# Electronic_Load.net
KiCad netlist of a schematic drawn in Altium Designer
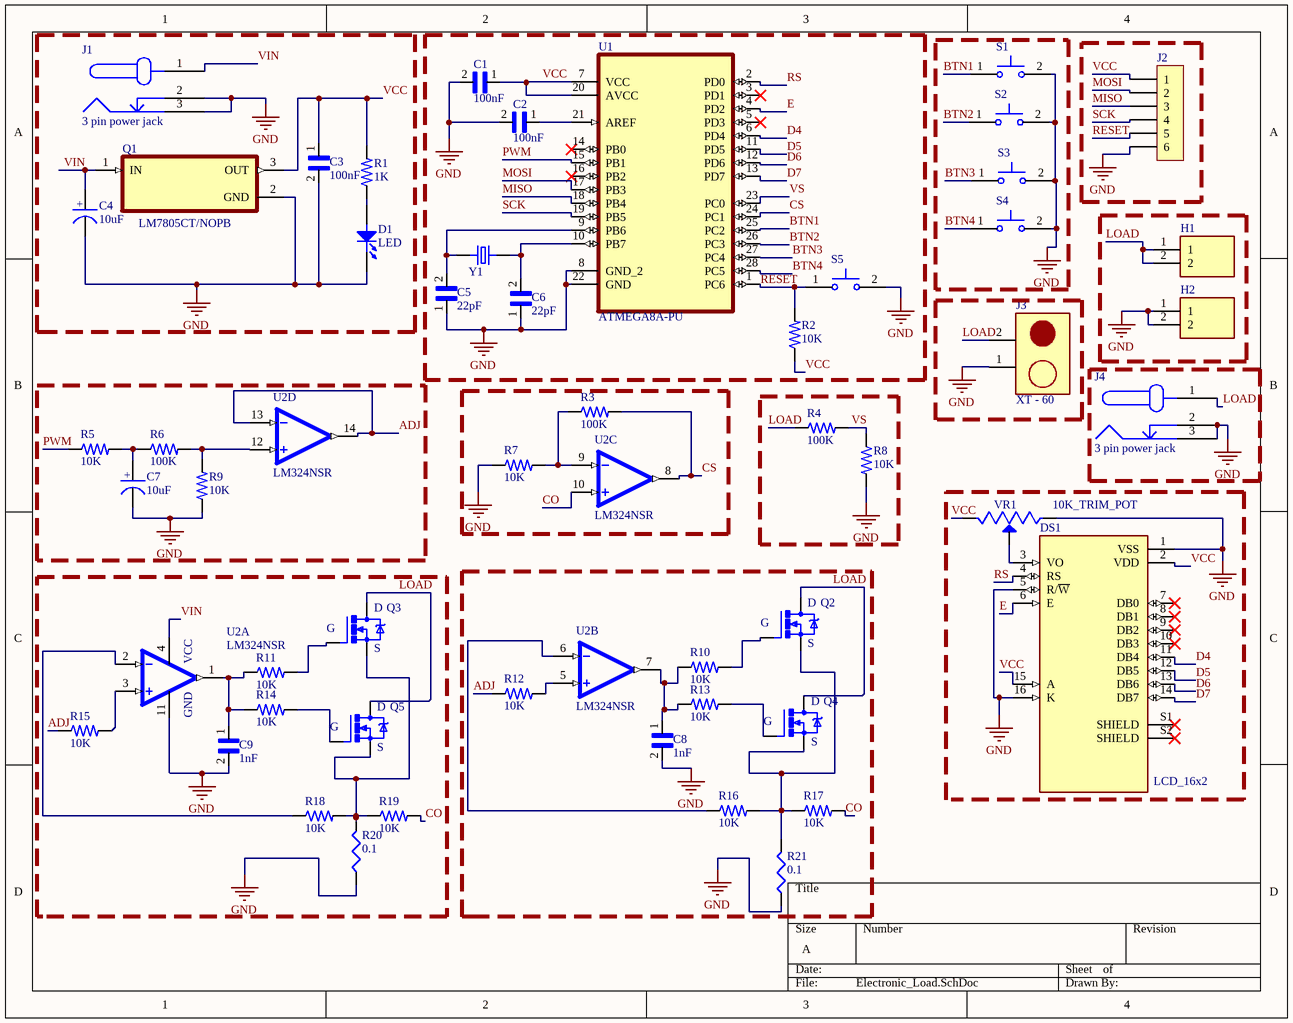
[diagram p0: Electronic_Load.SchDoc]

(export (version "E")
  (design (tool "Eeschema 10.0.6"))
  (components
    (comp (ref "C1")
      (value "100nF")
      (footprint "Cap_nonpolarized_2.5mm")
      (description "ceramic cap")
      (fields (field (name "MP") "GRM31CC80E157ME11K") (field (name "MF") "Murata"))
      (libsource (lib "Electronic_Load") (part "CAP1206"))
    )
    (comp (ref "C2")
      (value "100nF")
      (footprint "Cap_nonpolarized_2.5mm")
      (description "ceramic cap")
      (fields (field (name "MP") "GRM31CC80E157ME11K") (field (name "MF") "Murata"))
      (libsource (lib "Electronic_Load") (part "CAP1206"))
    )
    (comp (ref "C3")
      (value "100nF")
      (footprint "Cap_nonpolarized_2.5mm")
      (description "ceramic cap")
      (fields (field (name "MP") "GRM31CC80E157ME11K") (field (name "MF") "Murata"))
      (libsource (lib "") (part "CAP1206_1"))
    )
    (comp (ref "C4")
      (value "10uF")
      (footprint "CP_Radial_D4.0mm_P1.50mm")
      (description "Generial polarized capacitor for through hole or SMD capacitors")
      (libsource (lib "Electronic_Load") (part "Polarized capacitors"))
    )
    (comp (ref "C5")
      (value "22pF")
      (footprint "Cap_nonpolarized_2.5mm")
      (description "ceramic cap")
      (fields (field (name "MP") "GRM31CC80E157ME11K") (field (name "MF") "Murata"))
      (libsource (lib "") (part "CAP1206_2"))
    )
    (comp (ref "C6")
      (value "22pF")
      (footprint "Cap_nonpolarized_2.5mm")
      (description "ceramic cap")
      (fields (field (name "MP") "GRM31CC80E157ME11K") (field (name "MF") "Murata"))
      (libsource (lib "") (part "CAP1206_2"))
    )
    (comp (ref "C7")
      (value "10uF")
      (footprint "CP_Radial_D4.0mm_P1.50mm")
      (description "Generial polarized capacitor for through hole or SMD capacitors")
      (libsource (lib "Electronic_Load") (part "Polarized capacitors"))
    )
    (comp (ref "C8")
      (value "1nF")
      (footprint "Cap_nonpolarized_2.5mm")
      (description "ceramic cap")
      (fields (field (name "MP") "GRM31CC80E157ME11K") (field (name "MF") "Murata"))
      (libsource (lib "") (part "CAP1206_1"))
    )
    (comp (ref "C9")
      (value "1nF")
      (footprint "Cap_nonpolarized_2.5mm")
      (description "ceramic cap")
      (fields (field (name "MP") "GRM31CC80E157ME11K") (field (name "MF") "Murata"))
      (libsource (lib "") (part "CAP1206_1"))
    )
    (comp (ref "D1")
      (value "LED")
      (footprint "LED_TH_2.54mm")
      (libsource (lib "Electronic_Load") (part "LED"))
    )
    (comp (ref "DS1")
      (value "LCD_16x2")
      (footprint "LCD_16x2")
      (description "Display: LCD; alphanumeric; STN Negative; 16x2; blue; LED; PIN: 16")
      (fields (field (name "MF") "Raystar") (field (name "MP") "RC1602B-BIW-CSV"))
      (libsource (lib "Electronic_Load") (part "LCD_16x2"))
    )
    (comp (ref "H1")
      (value "Terminal PCB Male Flat 6.3mm")
      (footprint "Terminal PCB Male Flat 6.3mm")
      (description "PCR250 - Valcon PCB Mount Spade Terminal, 12.1mm PCB Profile")
      (fields (field (name "MP") "PCR250"))
      (libsource (lib "Electronic_Load") (part "Terminal PCB Male Flat 6.3mm"))
    )
    (comp (ref "H2")
      (value "Terminal PCB Male Flat 6.3mm")
      (footprint "Terminal PCB Male Flat 6.3mm")
      (description "PCR250 - Valcon PCB Mount Spade Terminal, 12.1mm PCB Profile")
      (fields (field (name "MP") "PCR250"))
      (libsource (lib "Electronic_Load") (part "Terminal PCB Male Flat 6.3mm"))
    )
    (comp (ref "J1")
      (value "3 pin power jack")
      (footprint "DC_POWER_JACK_2.7MM")
      (description "DC Power Jack / generic 3 pins connector")
      (libsource (lib "Electronic_Load") (part "DC Power Jack"))
    )
    (comp (ref "J2")
      (value "6 pin socket")
      (footprint "Jst - XH - 6pins")
      (libsource (lib "Electronic_Load") (part "Jst - XH -6pins"))
    )
    (comp (ref "J3")
      (value "XT - 60")
      (footprint "XT-60")
      (libsource (lib "Electronic_Load") (part "XT - 60"))
    )
    (comp (ref "J4")
      (value "3 pin power jack")
      (footprint "DC_POWER_JACK_2.7MM")
      (description "DC Power Jack / generic 3 pins connector")
      (libsource (lib "Electronic_Load") (part "DC Power Jack"))
    )
    (comp (ref "Q1")
      (value "LM7805CT/NOPB")
      (footprint "TO254P1054X470X1955-3")
      (libsource (lib "Electronic_Load") (part "LM7805CT/NOPB"))
    )
    (comp (ref "Q2")
      (value "NTP30N06L")
      (footprint "NTP30N06L")
      (description "N-Channel 100 V 9.2A (Tc) 3.7W (Ta), 60W (Tc) Surface Mount D2PAK")
      (fields (field (name "MP") "IRF520") (field (name "MF") "Vishay Siliconix"))
      (libsource (lib "Electronic_Load") (part "NTP30N06L"))
    )
    (comp (ref "Q3")
      (value "NTP30N06L")
      (footprint "NTP30N06L")
      (description "N-Channel 100 V 9.2A (Tc) 3.7W (Ta), 60W (Tc) Surface Mount D2PAK")
      (fields (field (name "MP") "IRF520") (field (name "MF") "Vishay Siliconix"))
      (libsource (lib "Electronic_Load") (part "NTP30N06L"))
    )
    (comp (ref "Q4")
      (value "NTP30N06L")
      (footprint "NTP30N06L")
      (description "N-Channel 100 V 9.2A (Tc) 3.7W (Ta), 60W (Tc) Surface Mount D2PAK")
      (fields (field (name "MP") "IRF520") (field (name "MF") "Vishay Siliconix"))
      (libsource (lib "Electronic_Load") (part "NTP30N06L"))
    )
    (comp (ref "Q5")
      (value "NTP30N06L")
      (footprint "NTP30N06L")
      (description "N-Channel 100 V 9.2A (Tc) 3.7W (Ta), 60W (Tc) Surface Mount D2PAK")
      (fields (field (name "MP") "IRF520") (field (name "MF") "Vishay Siliconix"))
      (libsource (lib "Electronic_Load") (part "NTP30N06L"))
    )
    (comp (ref "R1")
      (value "1K")
      (footprint "resistor_through hole")
      (description "RES 0.24 OHM 1% 1/4W 1206")
      (fields (field (name "MF") "TE Connectivity") (field (name "MP") "2-1879462-9"))
      (libsource (lib "Electronic_Load") (part "1206_RESISTOR"))
    )
    (comp (ref "R2")
      (value "10K")
      (footprint "resistor_through hole")
      (description "RES 0.24 OHM 1% 1/4W 1206")
      (fields (field (name "MF") "TE Connectivity") (field (name "MP") "2-1879462-9"))
      (libsource (lib "Electronic_Load") (part "1206_RESISTOR"))
    )
    (comp (ref "R3")
      (value "100K")
      (footprint "resistor_through hole")
      (description "RES 0.24 OHM 1% 1/4W 1206")
      (fields (field (name "MF") "TE Connectivity") (field (name "MP") "2-1879462-9"))
      (libsource (lib "Electronic_Load") (part "1206_RESISTOR"))
    )
    (comp (ref "R4")
      (value "100K")
      (footprint "resistor_through hole")
      (description "RES 0.24 OHM 1% 1/4W 1206")
      (fields (field (name "MF") "TE Connectivity") (field (name "MP") "2-1879462-9"))
      (libsource (lib "Electronic_Load") (part "1206_RESISTOR"))
    )
    (comp (ref "R5")
      (value "10K")
      (footprint "resistor_through hole")
      (description "RES 0.24 OHM 1% 1/4W 1206")
      (fields (field (name "MF") "TE Connectivity") (field (name "MP") "2-1879462-9"))
      (libsource (lib "Electronic_Load") (part "1206_RESISTOR"))
    )
    (comp (ref "R6")
      (value "100K")
      (footprint "resistor_through hole")
      (description "RES 0.24 OHM 1% 1/4W 1206")
      (fields (field (name "MF") "TE Connectivity") (field (name "MP") "2-1879462-9"))
      (libsource (lib "Electronic_Load") (part "1206_RESISTOR"))
    )
    (comp (ref "R7")
      (value "10K")
      (footprint "resistor_through hole")
      (description "RES 0.24 OHM 1% 1/4W 1206")
      (fields (field (name "MF") "TE Connectivity") (field (name "MP") "2-1879462-9"))
      (libsource (lib "Electronic_Load") (part "1206_RESISTOR"))
    )
    (comp (ref "R8")
      (value "10K")
      (footprint "resistor_through hole")
      (description "RES 0.24 OHM 1% 1/4W 1206")
      (fields (field (name "MF") "TE Connectivity") (field (name "MP") "2-1879462-9"))
      (libsource (lib "Electronic_Load") (part "1206_RESISTOR"))
    )
    (comp (ref "R9")
      (value "10K")
      (footprint "resistor_through hole")
      (description "RES 0.24 OHM 1% 1/4W 1206")
      (fields (field (name "MF") "TE Connectivity") (field (name "MP") "2-1879462-9"))
      (libsource (lib "Electronic_Load") (part "1206_RESISTOR"))
    )
    (comp (ref "R10")
      (value "10K")
      (footprint "resistor_through hole")
      (description "RES 0.24 OHM 1% 1/4W 1206")
      (fields (field (name "MF") "TE Connectivity") (field (name "MP") "2-1879462-9"))
      (libsource (lib "Electronic_Load") (part "1206_RESISTOR"))
    )
    (comp (ref "R11")
      (value "10K")
      (footprint "resistor_through hole")
      (description "RES 0.24 OHM 1% 1/4W 1206")
      (fields (field (name "MF") "TE Connectivity") (field (name "MP") "2-1879462-9"))
      (libsource (lib "Electronic_Load") (part "1206_RESISTOR"))
    )
    (comp (ref "R12")
      (value "10K")
      (footprint "resistor_through hole")
      (description "RES 0.24 OHM 1% 1/4W 1206")
      (fields (field (name "MF") "TE Connectivity") (field (name "MP") "2-1879462-9"))
      (libsource (lib "Electronic_Load") (part "1206_RESISTOR"))
    )
    (comp (ref "R13")
      (value "10K")
      (footprint "resistor_through hole")
      (description "RES 0.24 OHM 1% 1/4W 1206")
      (fields (field (name "MF") "TE Connectivity") (field (name "MP") "2-1879462-9"))
      (libsource (lib "Electronic_Load") (part "1206_RESISTOR"))
    )
    (comp (ref "R14")
      (value "10K")
      (footprint "resistor_through hole")
      (description "RES 0.24 OHM 1% 1/4W 1206")
      (fields (field (name "MF") "TE Connectivity") (field (name "MP") "2-1879462-9"))
      (libsource (lib "Electronic_Load") (part "1206_RESISTOR"))
    )
    (comp (ref "R15")
      (value "10K")
      (footprint "resistor_through hole")
      (description "RES 0.24 OHM 1% 1/4W 1206")
      (fields (field (name "MF") "TE Connectivity") (field (name "MP") "2-1879462-9"))
      (libsource (lib "Electronic_Load") (part "1206_RESISTOR"))
    )
    (comp (ref "R16")
      (value "10K")
      (footprint "resistor_through hole")
      (description "RES 0.24 OHM 1% 1/4W 1206")
      (fields (field (name "MF") "TE Connectivity") (field (name "MP") "2-1879462-9"))
      (libsource (lib "Electronic_Load") (part "1206_RESISTOR"))
    )
    (comp (ref "R17")
      (value "10K")
      (footprint "resistor_through hole")
      (description "RES 0.24 OHM 1% 1/4W 1206")
      (fields (field (name "MF") "TE Connectivity") (field (name "MP") "2-1879462-9"))
      (libsource (lib "Electronic_Load") (part "1206_RESISTOR"))
    )
    (comp (ref "R18")
      (value "10K")
      (footprint "resistor_through hole")
      (description "RES 0.24 OHM 1% 1/4W 1206")
      (fields (field (name "MF") "TE Connectivity") (field (name "MP") "2-1879462-9"))
      (libsource (lib "Electronic_Load") (part "1206_RESISTOR"))
    )
    (comp (ref "R19")
      (value "10K")
      (footprint "resistor_through hole")
      (description "RES 0.24 OHM 1% 1/4W 1206")
      (fields (field (name "MF") "TE Connectivity") (field (name "MP") "2-1879462-9"))
      (libsource (lib "Electronic_Load") (part "1206_RESISTOR"))
    )
    (comp (ref "R20")
      (value "0.1")
      (footprint "2W_resistor_through hole")
      (description "Generial resistor for through hole or SMD resistors")
      (libsource (lib "Electronic_Load") (part "US_Resistor"))
    )
    (comp (ref "R21")
      (value "0.1")
      (footprint "2W_resistor_through hole")
      (description "Generial resistor for through hole or SMD resistors")
      (libsource (lib "Electronic_Load") (part "US_Resistor"))
    )
    (comp (ref "S1")
      (value "BUTT-2")
      (footprint "SW_BUTT-2")
      (description "Tactile Switches MINI PUSH BUTTON SWITCH 2-PIN QTY. 4")
      (fields (field (name "MF") "Gravitech"))
      (libsource (lib "Electronic_Load") (part "BUTT-2"))
    )
    (comp (ref "S2")
      (value "BUTT-2")
      (footprint "SW_BUTT-2")
      (description "Tactile Switches MINI PUSH BUTTON SWITCH 2-PIN QTY. 4")
      (fields (field (name "MF") "Gravitech"))
      (libsource (lib "Electronic_Load") (part "BUTT-2"))
    )
    (comp (ref "S3")
      (value "BUTT-2")
      (footprint "SW_BUTT-2")
      (description "Tactile Switches MINI PUSH BUTTON SWITCH 2-PIN QTY. 4")
      (fields (field (name "MF") "Gravitech"))
      (libsource (lib "Electronic_Load") (part "BUTT-2"))
    )
    (comp (ref "S4")
      (value "BUTT-2")
      (footprint "SW_BUTT-2")
      (description "Tactile Switches MINI PUSH BUTTON SWITCH 2-PIN QTY. 4")
      (fields (field (name "MF") "Gravitech"))
      (libsource (lib "Electronic_Load") (part "BUTT-2"))
    )
    (comp (ref "S5")
      (value "BUTT-2")
      (footprint "SW_BUTT-2")
      (description "Tactile Switches MINI PUSH BUTTON SWITCH 2-PIN QTY. 4")
      (fields (field (name "MF") "Gravitech"))
      (libsource (lib "Electronic_Load") (part "BUTT-2"))
    )
    (comp (ref "U1")
      (value "ATMEGA8A-PU")
      (footprint "ATMEGA8A-PU")
      (description "AVR AVRÂ® ATmega Microcontroller IC 8-Bit 16MHz 8KB (4K x 16) FLASH 28-PDIP")
      (fields (field (name "MF") "Microchip"))
      (libsource (lib "Electronic_Load") (part "ATMEGA8A-PU"))
    )
    (comp (ref "U2")
      (value "LM324NSR")
      (footprint "DIP794W45P254L1969H508Q14")
      (description "4-Channel industry standard operational amplifier 14-SO 0 to 70")
      (fields (field (name "MF") "Texas Instruments"))
      (libsource (lib "Electronic_Load") (part "LM324NSR"))
    )
    (comp (ref "VR1")
      (value "10K_TRIM_POT")
      (footprint "TRIM_3296W-OT1-103LF")
      (description "Trimmer Resistors - Through Hole 3/8 SQ CERMET 10K SEALED TRIM POT")
      (fields (field (name "MF") "Bourns") (field (name "MP") "3296W-OT1-103LF"))
      (libsource (lib "Electronic_Load") (part "3296W-OT1-103LF"))
    )
    (comp (ref "Y1")
      (value "ECS-160-20-4X-DU")
      (footprint "XTAL_ECS-160-20-4X-DU")
      (description "16MHz Â±30ppm Crystal 20pF 40 Ohms HC-49/US")
      (fields (field (name "DIGI-KEY_PART_NUMBER") "XC1925-ND") (field (name "MF") "ECS Inc."))
      (libsource (lib "Electronic_Load") (part "ECS-160-20-4X-DU"))
    )
  )
  (nets
    (net (code "1") (name "/ADJ") (class "Default")
      (node (ref "R12") (pin "1") (pinfunction "1_1") (pintype "passive"))
      (node (ref "R15") (pin "1") (pinfunction "1_1") (pintype "passive"))
      (node (ref "U2") (pin "13") (pinfunction "4IN-_13") (pintype "input"))
      (node (ref "U2") (pin "14") (pinfunction "4OUT_14") (pintype "output"))
    )
    (net (code "2") (name "/BTN1") (class "Default")
      (node (ref "S1") (pin "1") (pinfunction "1_1") (pintype "passive"))
      (node (ref "U1") (pin "25") (pinfunction "PC2_25") (pintype "bidirectional"))
    )
    (net (code "3") (name "/BTN2") (class "Default")
      (node (ref "S2") (pin "1") (pinfunction "1_1") (pintype "passive"))
      (node (ref "U1") (pin "26") (pinfunction "PC3_26") (pintype "bidirectional"))
    )
    (net (code "4") (name "/BTN3") (class "Default")
      (node (ref "S3") (pin "1") (pinfunction "1_1") (pintype "passive"))
      (node (ref "U1") (pin "27") (pinfunction "PC4_27") (pintype "bidirectional"))
    )
    (net (code "5") (name "/BTN4") (class "Default")
      (node (ref "S4") (pin "1") (pinfunction "1_1") (pintype "passive"))
      (node (ref "U1") (pin "28") (pinfunction "PC5_28") (pintype "bidirectional"))
    )
    (net (code "6") (name "/CO") (class "Default")
      (node (ref "R17") (pin "2") (pinfunction "2_2") (pintype "passive"))
      (node (ref "R19") (pin "2") (pinfunction "2_2") (pintype "passive"))
      (node (ref "U2") (pin "10") (pinfunction "3IN+_10") (pintype "input"))
    )
    (net (code "7") (name "/CS") (class "Default")
      (node (ref "R3") (pin "2") (pinfunction "2_2") (pintype "passive"))
      (node (ref "U1") (pin "24") (pinfunction "PC1_24") (pintype "bidirectional"))
      (node (ref "U2") (pin "8") (pinfunction "3OUT_8") (pintype "output"))
    )
    (net (code "8") (name "/D4") (class "Default")
      (node (ref "DS1") (pin "11") (pinfunction "DB4_11") (pintype "bidirectional"))
      (node (ref "U1") (pin "6") (pinfunction "PD4_6") (pintype "bidirectional"))
    )
    (net (code "9") (name "/D5") (class "Default")
      (node (ref "DS1") (pin "12") (pinfunction "DB5_12") (pintype "bidirectional"))
      (node (ref "U1") (pin "11") (pinfunction "PD5_11") (pintype "bidirectional"))
    )
    (net (code "10") (name "/D6") (class "Default")
      (node (ref "DS1") (pin "13") (pinfunction "DB6_13") (pintype "bidirectional"))
      (node (ref "U1") (pin "12") (pinfunction "PD6_12") (pintype "bidirectional"))
    )
    (net (code "11") (name "/D7") (class "Default")
      (node (ref "DS1") (pin "14") (pinfunction "DB7_14") (pintype "bidirectional"))
      (node (ref "U1") (pin "13") (pinfunction "PD7_13") (pintype "bidirectional"))
    )
    (net (code "12") (name "/E") (class "Default")
      (node (ref "DS1") (pin "6") (pinfunction "E_6") (pintype "input"))
      (node (ref "U1") (pin "4") (pinfunction "PD2_4") (pintype "bidirectional"))
    )
    (net (code "13") (name "/LOAD") (class "Default")
      (node (ref "H1") (pin "1") (pinfunction "1_1") (pintype "passive"))
      (node (ref "H1") (pin "2") (pinfunction "2_2") (pintype "passive"))
      (node (ref "J3") (pin "2") (pinfunction "-_2") (pintype "passive"))
      (node (ref "J4") (pin "1") (pinfunction "1_1") (pintype "passive"))
      (node (ref "Q2") (pin "2") (pinfunction "D_2") (pintype "passive"))
      (node (ref "Q3") (pin "2") (pinfunction "D_2") (pintype "passive"))
      (node (ref "Q4") (pin "2") (pinfunction "D_2") (pintype "passive"))
      (node (ref "Q5") (pin "2") (pinfunction "D_2") (pintype "passive"))
      (node (ref "R4") (pin "1") (pinfunction "1_1") (pintype "passive"))
    )
    (net (code "14") (name "/MISO") (class "Default")
      (node (ref "J2") (pin "3") (pinfunction "3_3") (pintype "passive"))
      (node (ref "U1") (pin "18") (pinfunction "PB4_18") (pintype "bidirectional"))
    )
    (net (code "15") (name "/MOSI") (class "Default")
      (node (ref "J2") (pin "2") (pinfunction "2_2") (pintype "passive"))
      (node (ref "U1") (pin "17") (pinfunction "PB3_17") (pintype "bidirectional"))
    )
    (net (code "16") (name "/PWM") (class "Default")
      (node (ref "R5") (pin "1") (pinfunction "1_1") (pintype "passive"))
      (node (ref "U1") (pin "15") (pinfunction "PB1_15") (pintype "bidirectional"))
    )
    (net (code "17") (name "/RESET") (class "Default")
      (node (ref "J2") (pin "5") (pinfunction "5_5") (pintype "passive"))
      (node (ref "R2") (pin "2") (pinfunction "2_2") (pintype "passive"))
      (node (ref "S5") (pin "1") (pinfunction "1_1") (pintype "passive"))
      (node (ref "U1") (pin "1") (pinfunction "PC6_1") (pintype "bidirectional"))
    )
    (net (code "18") (name "/RS") (class "Default")
      (node (ref "DS1") (pin "4") (pinfunction "RS_4") (pintype "bidirectional"))
      (node (ref "U1") (pin "2") (pinfunction "PD0_2") (pintype "bidirectional"))
    )
    (net (code "19") (name "/SCK") (class "Default")
      (node (ref "J2") (pin "4") (pinfunction "4_4") (pintype "passive"))
      (node (ref "U1") (pin "19") (pinfunction "PB5_19") (pintype "bidirectional"))
    )
    (net (code "20") (name "/VCC") (class "Default")
      (node (ref "C1") (pin "1") (pinfunction "1_1") (pintype "passive"))
      (node (ref "C3") (pin "1") (pinfunction "1_1") (pintype "passive"))
      (node (ref "DS1") (pin "15") (pinfunction "A_15") (pintype "input"))
      (node (ref "DS1") (pin "2") (pinfunction "VDD_2") (pintype "power_in"))
      (node (ref "J2") (pin "1") (pinfunction "1_1") (pintype "passive"))
      (node (ref "Q1") (pin "3") (pinfunction "OUT_3") (pintype "output"))
      (node (ref "R1") (pin "2") (pinfunction "2_2") (pintype "passive"))
      (node (ref "R2") (pin "1") (pinfunction "1_1") (pintype "passive"))
      (node (ref "U1") (pin "20") (pinfunction "AVCC_20") (pintype "power_in"))
      (node (ref "U1") (pin "7") (pinfunction "VCC_7") (pintype "power_in"))
      (node (ref "VR1") (pin "3") (pinfunction "CW_3") (pintype "passive"))
    )
    (net (code "21") (name "/VIN") (class "Default")
      (node (ref "C4") (pin "1") (pinfunction "Positive_1") (pintype "passive"))
      (node (ref "J1") (pin "1") (pinfunction "1_1") (pintype "passive"))
      (node (ref "Q1") (pin "1") (pinfunction "IN_1") (pintype "input"))
      (node (ref "U2") (pin "4") (pinfunction "VCC_4") (pintype "power_in"))
    )
    (net (code "22") (name "/VS") (class "Default")
      (node (ref "R4") (pin "2") (pinfunction "2_2") (pintype "passive"))
      (node (ref "R8") (pin "1") (pinfunction "1_1") (pintype "passive"))
      (node (ref "U1") (pin "23") (pinfunction "PC0_23") (pintype "bidirectional"))
    )
    (net (code "23") (name "GND") (class "Default")
      (node (ref "C1") (pin "2") (pinfunction "2_2") (pintype "passive"))
      (node (ref "C2") (pin "2") (pinfunction "2_2") (pintype "passive"))
      (node (ref "C3") (pin "2") (pinfunction "2_2") (pintype "passive"))
      (node (ref "C4") (pin "2") (pinfunction "Negative_2") (pintype "passive"))
      (node (ref "C5") (pin "1") (pinfunction "1_1") (pintype "passive"))
      (node (ref "C6") (pin "1") (pinfunction "1_1") (pintype "passive"))
      (node (ref "C7") (pin "2") (pinfunction "Negative_2") (pintype "passive"))
      (node (ref "C8") (pin "2") (pinfunction "2_2") (pintype "passive"))
      (node (ref "C9") (pin "2") (pinfunction "2_2") (pintype "passive"))
      (node (ref "D1") (pin "2") (pinfunction "Negative_2") (pintype "passive"))
      (node (ref "DS1") (pin "1") (pinfunction "VSS_1") (pintype "power_in"))
      (node (ref "DS1") (pin "16") (pinfunction "K_16") (pintype "input"))
      (node (ref "DS1") (pin "5") (pinfunction "R/~{W}_5") (pintype "bidirectional"))
      (node (ref "H2") (pin "1") (pinfunction "1_1") (pintype "passive"))
      (node (ref "H2") (pin "2") (pinfunction "2_2") (pintype "passive"))
      (node (ref "J1") (pin "2") (pinfunction "2_2") (pintype "passive"))
      (node (ref "J1") (pin "3") (pinfunction "3_3") (pintype "passive"))
      (node (ref "J2") (pin "6") (pinfunction "6_6") (pintype "passive"))
      (node (ref "J3") (pin "1") (pinfunction "+_1") (pintype "passive"))
      (node (ref "J4") (pin "2") (pinfunction "2_2") (pintype "passive"))
      (node (ref "J4") (pin "3") (pinfunction "3_3") (pintype "passive"))
      (node (ref "Q1") (pin "2") (pinfunction "GND_2") (pintype "power_in"))
      (node (ref "R20") (pin "1") (pinfunction "1_1") (pintype "passive"))
      (node (ref "R21") (pin "1") (pinfunction "1_1") (pintype "passive"))
      (node (ref "R7") (pin "1") (pinfunction "1_1") (pintype "passive"))
      (node (ref "R8") (pin "2") (pinfunction "2_2") (pintype "passive"))
      (node (ref "R9") (pin "1") (pinfunction "1_1") (pintype "passive"))
      (node (ref "S1") (pin "2") (pinfunction "2_2") (pintype "passive"))
      (node (ref "S2") (pin "2") (pinfunction "2_2") (pintype "passive"))
      (node (ref "S3") (pin "2") (pinfunction "2_2") (pintype "passive"))
      (node (ref "S4") (pin "2") (pinfunction "2_2") (pintype "passive"))
      (node (ref "S5") (pin "2") (pinfunction "2_2") (pintype "passive"))
      (node (ref "U1") (pin "22") (pinfunction "GND_22") (pintype "passive"))
      (node (ref "U1") (pin "8") (pinfunction "GND_2_8") (pintype "passive"))
      (node (ref "U2") (pin "11") (pinfunction "GND_11") (pintype "power_in"))
      (node (ref "VR1") (pin "1") (pinfunction "CCW_1") (pintype "passive"))
    )
    (net (code "24") (name "Net-(C7-Positive)") (class "Default")
      (node (ref "C7") (pin "1") (pinfunction "Positive_1") (pintype "passive"))
      (node (ref "R5") (pin "2") (pinfunction "2_2") (pintype "passive"))
      (node (ref "R6") (pin "1") (pinfunction "1_1") (pintype "passive"))
    )
    (net (code "25") (name "Net-(D1-Positive)") (class "Default")
      (node (ref "D1") (pin "1") (pinfunction "Positive_1") (pintype "passive"))
      (node (ref "R1") (pin "1") (pinfunction "1_1") (pintype "passive"))
    )
    (net (code "26") (name "Net-(DS1-VO)") (class "Default")
      (node (ref "DS1") (pin "3") (pinfunction "VO_3") (pintype "input"))
      (node (ref "VR1") (pin "2") (pinfunction "WIPER_2") (pintype "passive"))
    )
    (net (code "27") (name "Net-(Q2-G)") (class "Default")
      (node (ref "Q2") (pin "1") (pinfunction "G_1") (pintype "passive"))
      (node (ref "R10") (pin "2") (pinfunction "2_2") (pintype "passive"))
    )
    (net (code "28") (name "Net-(Q2-S)") (class "Default")
      (node (ref "Q2") (pin "3") (pinfunction "S_3") (pintype "passive"))
      (node (ref "Q4") (pin "3") (pinfunction "S_3") (pintype "passive"))
      (node (ref "R16") (pin "2") (pinfunction "2_2") (pintype "passive"))
      (node (ref "R17") (pin "1") (pinfunction "1_1") (pintype "passive"))
      (node (ref "R21") (pin "2") (pinfunction "2_2") (pintype "passive"))
    )
    (net (code "29") (name "Net-(Q3-G)") (class "Default")
      (node (ref "Q3") (pin "1") (pinfunction "G_1") (pintype "passive"))
      (node (ref "R11") (pin "2") (pinfunction "2_2") (pintype "passive"))
    )
    (net (code "30") (name "Net-(Q3-S)") (class "Default")
      (node (ref "Q3") (pin "3") (pinfunction "S_3") (pintype "passive"))
      (node (ref "Q5") (pin "3") (pinfunction "S_3") (pintype "passive"))
      (node (ref "R18") (pin "2") (pinfunction "2_2") (pintype "passive"))
      (node (ref "R19") (pin "1") (pinfunction "1_1") (pintype "passive"))
      (node (ref "R20") (pin "2") (pinfunction "2_2") (pintype "passive"))
    )
    (net (code "31") (name "Net-(Q4-G)") (class "Default")
      (node (ref "Q4") (pin "1") (pinfunction "G_1") (pintype "passive"))
      (node (ref "R13") (pin "2") (pinfunction "2_2") (pintype "passive"))
    )
    (net (code "32") (name "Net-(Q5-G)") (class "Default")
      (node (ref "Q5") (pin "1") (pinfunction "G_1") (pintype "passive"))
      (node (ref "R14") (pin "2") (pinfunction "2_2") (pintype "passive"))
    )
    (net (code "33") (name "Net-(U1-AREF)") (class "Default")
      (node (ref "C2") (pin "1") (pinfunction "1_1") (pintype "passive"))
      (node (ref "U1") (pin "21") (pinfunction "AREF_21") (pintype "input"))
    )
    (net (code "34") (name "Net-(U1-PB6)") (class "Default")
      (node (ref "C5") (pin "2") (pinfunction "2_2") (pintype "passive"))
      (node (ref "U1") (pin "9") (pinfunction "PB6_9") (pintype "bidirectional"))
      (node (ref "Y1") (pin "2") (pinfunction "2_2") (pintype "passive"))
    )
    (net (code "35") (name "Net-(U1-PB7)") (class "Default")
      (node (ref "C6") (pin "2") (pinfunction "2_2") (pintype "passive"))
      (node (ref "U1") (pin "10") (pinfunction "PB7_10") (pintype "bidirectional"))
      (node (ref "Y1") (pin "1") (pinfunction "1_1") (pintype "passive"))
    )
    (net (code "36") (name "Net-(U2A-1IN+)") (class "Default")
      (node (ref "R15") (pin "2") (pinfunction "2_2") (pintype "passive"))
      (node (ref "U2") (pin "3") (pinfunction "1IN+_3") (pintype "input"))
    )
    (net (code "37") (name "Net-(U2A-1IN-)") (class "Default")
      (node (ref "R18") (pin "1") (pinfunction "1_1") (pintype "passive"))
      (node (ref "U2") (pin "2") (pinfunction "1IN-_2") (pintype "input"))
    )
    (net (code "38") (name "Net-(U2A-1OUT)") (class "Default")
      (node (ref "C9") (pin "1") (pinfunction "1_1") (pintype "passive"))
      (node (ref "R11") (pin "1") (pinfunction "1_1") (pintype "passive"))
      (node (ref "R14") (pin "1") (pinfunction "1_1") (pintype "passive"))
      (node (ref "U2") (pin "1") (pinfunction "1OUT_1") (pintype "output"))
    )
    (net (code "39") (name "Net-(U2B-2IN+)") (class "Default")
      (node (ref "R12") (pin "2") (pinfunction "2_2") (pintype "passive"))
      (node (ref "U2") (pin "5") (pinfunction "2IN+_5") (pintype "input"))
    )
    (net (code "40") (name "Net-(U2B-2IN-)") (class "Default")
      (node (ref "R16") (pin "1") (pinfunction "1_1") (pintype "passive"))
      (node (ref "U2") (pin "6") (pinfunction "2IN-_6") (pintype "input"))
    )
    (net (code "41") (name "Net-(U2B-2OUT)") (class "Default")
      (node (ref "C8") (pin "1") (pinfunction "1_1") (pintype "passive"))
      (node (ref "R10") (pin "1") (pinfunction "1_1") (pintype "passive"))
      (node (ref "R13") (pin "1") (pinfunction "1_1") (pintype "passive"))
      (node (ref "U2") (pin "7") (pinfunction "2OUT_7") (pintype "output"))
    )
    (net (code "42") (name "Net-(U2C-3IN-)") (class "Default")
      (node (ref "R3") (pin "1") (pinfunction "1_1") (pintype "passive"))
      (node (ref "R7") (pin "2") (pinfunction "2_2") (pintype "passive"))
      (node (ref "U2") (pin "9") (pinfunction "3IN-_9") (pintype "input"))
    )
    (net (code "43") (name "Net-(U2D-4IN+)") (class "Default")
      (node (ref "R6") (pin "2") (pinfunction "2_2") (pintype "passive"))
      (node (ref "R9") (pin "2") (pinfunction "2_2") (pintype "passive"))
      (node (ref "U2") (pin "12") (pinfunction "4IN+_12") (pintype "input"))
    )
    (net (code "44") (name "unconnected-(DS1-DB0-Pad7)") (class "Default")
      (node (ref "DS1") (pin "7") (pinfunction "DB0_7") (pintype "bidirectional+no_connect"))
    )
    (net (code "45") (name "unconnected-(DS1-DB1-Pad8)") (class "Default")
      (node (ref "DS1") (pin "8") (pinfunction "DB1_8") (pintype "bidirectional+no_connect"))
    )
    (net (code "46") (name "unconnected-(DS1-DB2-Pad9)") (class "Default")
      (node (ref "DS1") (pin "9") (pinfunction "DB2_9") (pintype "bidirectional"))
    )
    (net (code "47") (name "unconnected-(DS1-DB3-Pad10)") (class "Default")
      (node (ref "DS1") (pin "10") (pinfunction "DB3_10") (pintype "bidirectional+no_connect"))
    )
    (net (code "48") (name "unconnected-(DS1-SHIELD-PadS1)") (class "Default")
      (node (ref "DS1") (pin "S1") (pinfunction "SHIELD_S1") (pintype "passive+no_connect"))
    )
    (net (code "49") (name "unconnected-(DS1-SHIELD-PadS2)") (class "Default")
      (node (ref "DS1") (pin "S2") (pinfunction "SHIELD_S2") (pintype "passive+no_connect"))
    )
    (net (code "50") (name "unconnected-(U1-PB0-Pad14)") (class "Default")
      (node (ref "U1") (pin "14") (pinfunction "PB0_14") (pintype "bidirectional+no_connect"))
    )
    (net (code "51") (name "unconnected-(U1-PB2-Pad16)") (class "Default")
      (node (ref "U1") (pin "16") (pinfunction "PB2_16") (pintype "bidirectional+no_connect"))
    )
    (net (code "52") (name "unconnected-(U1-PD1-Pad3)") (class "Default")
      (node (ref "U1") (pin "3") (pinfunction "PD1_3") (pintype "bidirectional+no_connect"))
    )
    (net (code "53") (name "unconnected-(U1-PD3-Pad5)") (class "Default")
      (node (ref "U1") (pin "5") (pinfunction "PD3_5") (pintype "bidirectional+no_connect"))
    )
  )
)
